# gasPrs_SingleChannel.net
KiCad netlist of a schematic drawn in Altium Designer
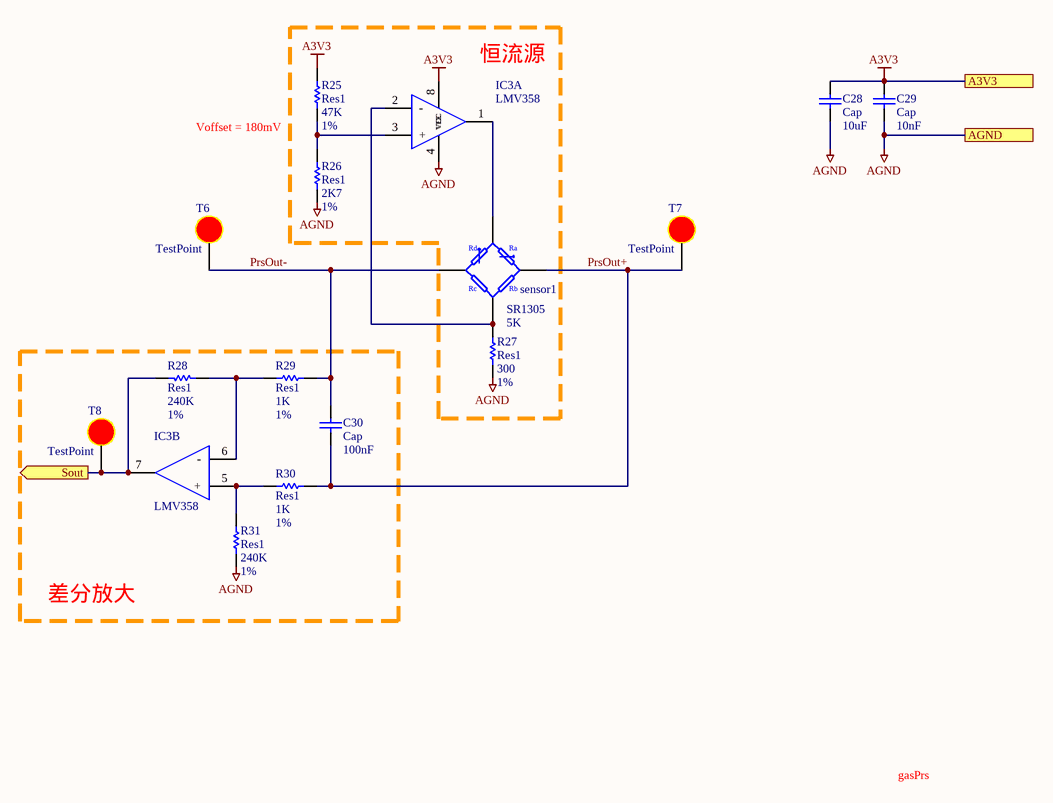
[diagram p0: gasPrs_SingleChannel.SchDoc]

(export (version "E")
  (design (tool "Eeschema 10.0.6"))
  (components
    (comp (ref "C28")
      (value "Cap")
      (footprint "0603C")
      (description "Capacitor")
      (fields (field (name "ALTIUM_VALUE") "10uF") (field (name "PUBLISHER") "Altium Limited"))
      (libsource (lib "Miscellaneous Devices") (part "Cap"))
    )
    (comp (ref "C29")
      (value "Cap")
      (footprint "0603C")
      (description "Capacitor")
      (fields (field (name "ALTIUM_VALUE") "10nF") (field (name "PUBLISHER") "Altium Limited"))
      (libsource (lib "Miscellaneous Devices") (part "Cap"))
    )
    (comp (ref "C30")
      (value "Cap")
      (footprint "0603C")
      (description "Capacitor")
      (fields (field (name "ALTIUM_VALUE") "100nF") (field (name "PUBLISHER") "Altium Limited"))
      (libsource (lib "Miscellaneous Devices") (part "Cap"))
    )
    (comp (ref "IC3")
      (value "LMV358")
      (footprint "脉诊:SOIC127P600X175-8N")
      (description "Integrated Circuit")
      (fields
        (field (name "MANUFACTURER_PART_NUMBER") "LMV358MX/NOPB")
        (field (name "MOUSER PART NUMBER") "926-LMV358MX/NOPB")
      )
      (libsource (lib "脉诊") (part "LMV358MX_NOPB"))
    )
    (comp (ref "R25")
      (value "Res1")
      (footprint "0603R")
      (description "Resistor")
      (fields
        (field (name "ALTIUM_VALUE") "47K")
        (field (name "DELTA") "1%")
        (field (name "PUBLISHER") "Altium Limited")
      )
      (libsource (lib "Miscellaneous Devices") (part "Res1"))
    )
    (comp (ref "R26")
      (value "Res1")
      (footprint "0603R")
      (description "Resistor")
      (fields
        (field (name "ALTIUM_VALUE") "2K7")
        (field (name "DELTA") "1%")
        (field (name "PUBLISHER") "Altium Limited")
      )
      (libsource (lib "Miscellaneous Devices") (part "Res1"))
    )
    (comp (ref "R27")
      (value "Res1")
      (footprint "0603R")
      (description "Resistor")
      (fields
        (field (name "ALTIUM_VALUE") "300")
        (field (name "DELTA") "1%")
        (field (name "PUBLISHER") "Altium Limited")
      )
      (libsource (lib "Miscellaneous Devices") (part "Res1"))
    )
    (comp (ref "R28")
      (value "Res1")
      (footprint "0603R")
      (description "Resistor")
      (fields
        (field (name "ALTIUM_VALUE") "240K")
        (field (name "DELTA") "1%")
        (field (name "PUBLISHER") "Altium Limited")
      )
      (libsource (lib "Miscellaneous Devices") (part "Res1"))
    )
    (comp (ref "R29")
      (value "Res1")
      (footprint "0603R")
      (description "Resistor")
      (fields
        (field (name "ALTIUM_VALUE") "1K")
        (field (name "DELTA") "1%")
        (field (name "PUBLISHER") "Altium Limited")
      )
      (libsource (lib "Miscellaneous Devices") (part "Res1"))
    )
    (comp (ref "R30")
      (value "Res1")
      (footprint "0603R")
      (description "Resistor")
      (fields
        (field (name "ALTIUM_VALUE") "1K")
        (field (name "DELTA") "1%")
        (field (name "PUBLISHER") "Altium Limited")
      )
      (libsource (lib "Miscellaneous Devices") (part "Res1"))
    )
    (comp (ref "R31")
      (value "Res1")
      (footprint "0603R")
      (description "Resistor")
      (fields
        (field (name "ALTIUM_VALUE") "240K")
        (field (name "DELTA") "1%")
        (field (name "PUBLISHER") "Altium Limited")
      )
      (libsource (lib "Miscellaneous Devices") (part "Res1"))
    )
    (comp (ref "sensor1")
      (value "SR1305")
      (footprint "SENSON")
      (description "Resistor Bridge")
      (fields (field (name "ALTIUM_VALUE") "5K") (field (name "PUBLISHER") "Altium Limited"))
      (libsource (lib "Miscellaneous Devices") (part "Res Bridge"))
    )
    (comp (ref "T6")
      (value "TestPoint")
      (footprint "TP_D1mm")
      (description "测试点")
      (libsource (lib "脉诊") (part "TP"))
    )
    (comp (ref "T7")
      (value "TestPoint")
      (footprint "TP_D1mm")
      (description "测试点")
      (libsource (lib "脉诊") (part "TP"))
    )
    (comp (ref "T8")
      (value "TestPoint")
      (footprint "TP_D1mm")
      (description "测试点")
      (libsource (lib "脉诊") (part "TP"))
    )
  )
  (nets
    (net (code "1") (name "/PrsOut+") (class "Default")
      (node (ref "C30") (pin "1") (pinfunction "1_1") (pintype "passive"))
      (node (ref "R30") (pin "1") (pinfunction "1_1") (pintype "passive"))
      (node (ref "T7") (pin "9") (pinfunction "1_9") (pintype "passive"))
      (node (ref "sensor1") (pin "2") (pinfunction "2_2") (pintype "passive"))
    )
    (net (code "2") (name "/PrsOut-") (class "Default")
      (node (ref "C30") (pin "2") (pinfunction "2_2") (pintype "passive"))
      (node (ref "R29") (pin "1") (pinfunction "1_1") (pintype "passive"))
      (node (ref "T6") (pin "9") (pinfunction "1_9") (pintype "passive"))
      (node (ref "sensor1") (pin "4") (pinfunction "4_4") (pintype "passive"))
    )
    (net (code "3") (name "/Sout") (class "Default")
      (node (ref "IC3") (pin "7") (pinfunction "OUTB_7") (pintype "passive"))
      (node (ref "R28") (pin "1") (pinfunction "1_1") (pintype "passive"))
      (node (ref "T8") (pin "9") (pinfunction "1_9") (pintype "passive"))
    )
    (net (code "4") (name "A3V3") (class "Default")
      (node (ref "C28") (pin "2") (pinfunction "2_2") (pintype "passive"))
      (node (ref "C29") (pin "2") (pinfunction "2_2") (pintype "passive"))
      (node (ref "IC3") (pin "8") (pinfunction "VCC_8") (pintype "passive"))
      (node (ref "R25") (pin "1") (pinfunction "1_1") (pintype "passive"))
    )
    (net (code "5") (name "AGND") (class "Default")
      (node (ref "C28") (pin "1") (pinfunction "1_1") (pintype "passive"))
      (node (ref "C29") (pin "1") (pinfunction "1_1") (pintype "passive"))
      (node (ref "IC3") (pin "4") (pinfunction "VEE_4") (pintype "passive"))
      (node (ref "R26") (pin "2") (pinfunction "2_2") (pintype "passive"))
      (node (ref "R27") (pin "1") (pinfunction "1_1") (pintype "passive"))
      (node (ref "R31") (pin "1") (pinfunction "1_1") (pintype "passive"))
    )
    (net (code "6") (name "Net-(IC3A-+)") (class "Default")
      (node (ref "IC3") (pin "3") (pinfunction "+_3") (pintype "passive"))
      (node (ref "R25") (pin "2") (pinfunction "2_2") (pintype "passive"))
      (node (ref "R26") (pin "1") (pinfunction "1_1") (pintype "passive"))
    )
    (net (code "7") (name "Net-(IC3A--)") (class "Default")
      (node (ref "IC3") (pin "2") (pinfunction "-_2") (pintype "passive"))
      (node (ref "R27") (pin "2") (pinfunction "2_2") (pintype "passive"))
      (node (ref "sensor1") (pin "3") (pinfunction "3_3") (pintype "passive"))
    )
    (net (code "8") (name "Net-(IC3A-OUTA)") (class "Default")
      (node (ref "IC3") (pin "1") (pinfunction "OUTA_1") (pintype "passive"))
      (node (ref "sensor1") (pin "1") (pinfunction "1_1") (pintype "passive"))
    )
    (net (code "9") (name "Net-(IC3B-+)") (class "Default")
      (node (ref "IC3") (pin "5") (pinfunction "+_5") (pintype "passive"))
      (node (ref "R30") (pin "2") (pinfunction "2_2") (pintype "passive"))
      (node (ref "R31") (pin "2") (pinfunction "2_2") (pintype "passive"))
    )
    (net (code "10") (name "Net-(IC3B--)") (class "Default")
      (node (ref "IC3") (pin "6") (pinfunction "-_6") (pintype "passive"))
      (node (ref "R28") (pin "2") (pinfunction "2_2") (pintype "passive"))
      (node (ref "R29") (pin "2") (pinfunction "2_2") (pintype "passive"))
    )
  )
)
